# RedCarMotorControllerBoard.net
KiCad netlist of a schematic drawn in EAGLE
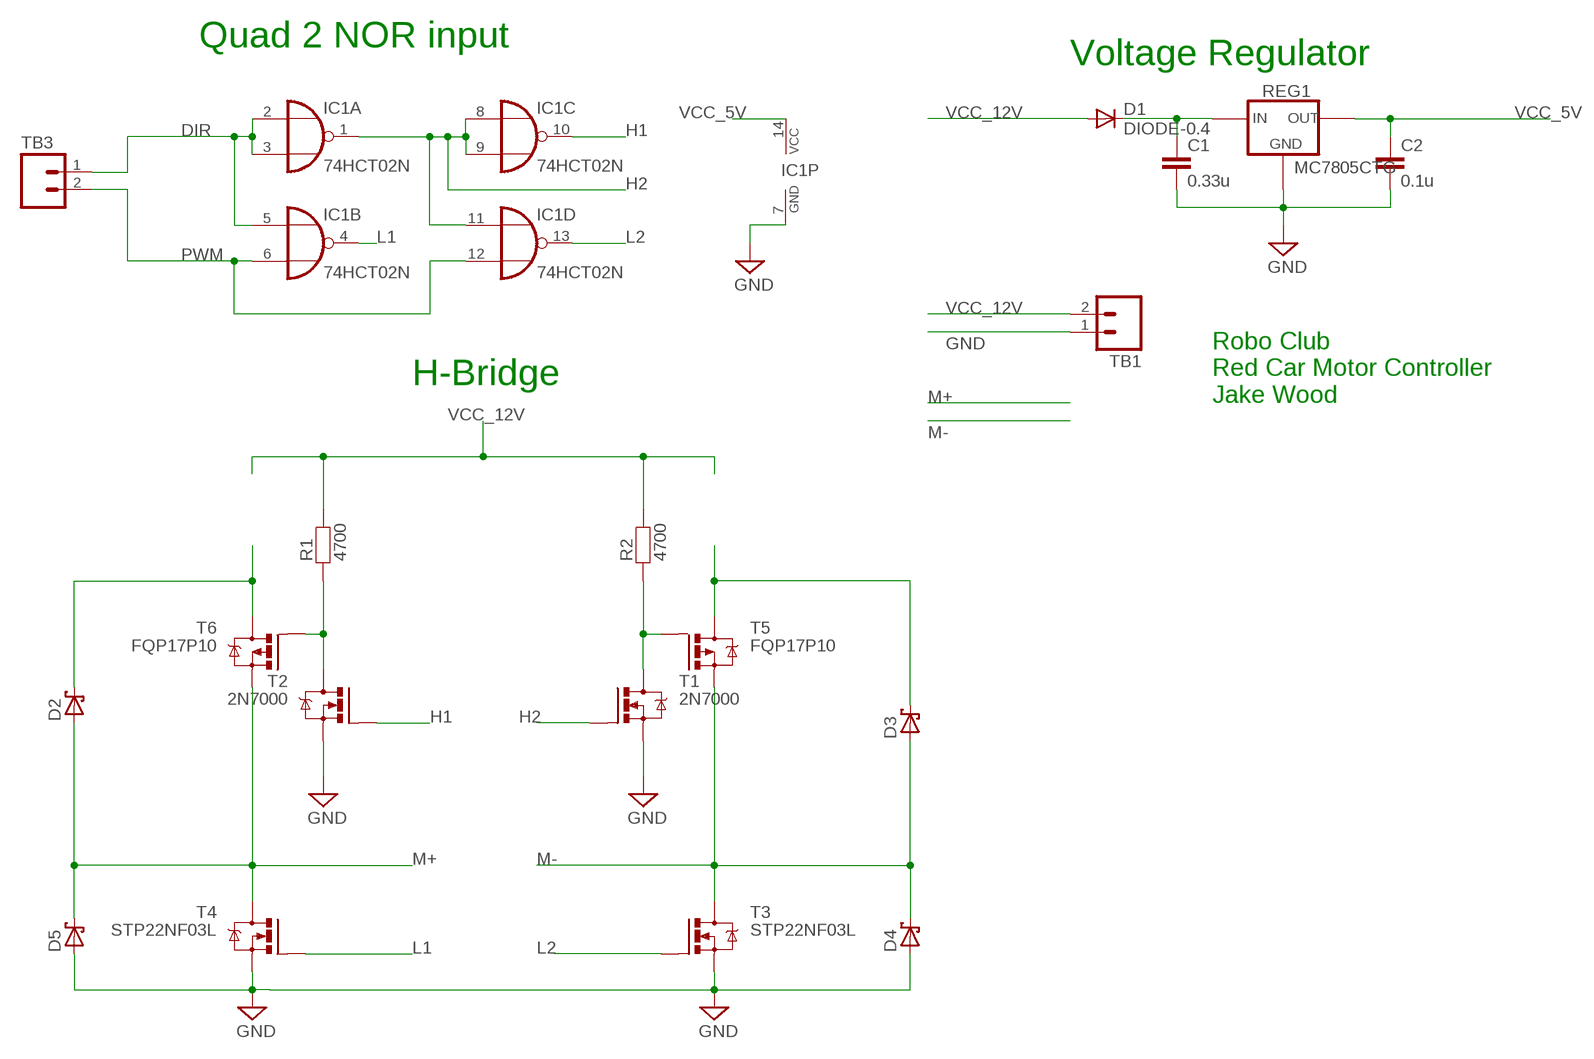
[diagram p0: schematic, sheet 1]

(export (version "E")
  (design (tool "Eeschema 10.0.6"))
  (components
    (comp (ref "C1")
      (value "0.33u")
      (footprint "eagle-import:RADIAL-0.2")
      (libsource (lib "eagle-import") (part "CAPACITOR-RADIAL-0.2"))
    )
    (comp (ref "C2")
      (value "0.1u")
      (footprint "eagle-import:RADIAL-0.2")
      (libsource (lib "eagle-import") (part "CAPACITOR-RADIAL-0.2"))
    )
    (comp (ref "D1")
      (value "DIODE-0.4")
      (footprint "eagle-import:DIODE-0.4")
      (libsource (lib "eagle-import") (part "DIODE-0.4"))
    )
    (comp (ref "D2")
      (value "SCHOTTKY-DIODEDO201T15")
      (footprint "eagle-import:DO201T15")
      (libsource (lib "eagle-import") (part "SCHOTTKY-DIODEDO201T15"))
    )
    (comp (ref "D3")
      (value "SCHOTTKY-DIODEDO201T15")
      (footprint "eagle-import:DO201T15")
      (libsource (lib "eagle-import") (part "SCHOTTKY-DIODEDO201T15"))
    )
    (comp (ref "D4")
      (value "SCHOTTKY-DIODEDO201T15")
      (footprint "eagle-import:DO201T15")
      (libsource (lib "eagle-import") (part "SCHOTTKY-DIODEDO201T15"))
    )
    (comp (ref "D5")
      (value "SCHOTTKY-DIODEDO201T15")
      (footprint "eagle-import:DO201T15")
      (libsource (lib "eagle-import") (part "SCHOTTKY-DIODEDO201T15"))
    )
    (comp (ref "IC1")
      (value "74HCT02N")
      (footprint "eagle-import:DIL14")
      (libsource (lib "eagle-import") (part "7402NHCT"))
    )
    (comp (ref "R1")
      (value "4700")
      (footprint "eagle-import:AXIAL-0.4")
      (libsource (lib "eagle-import") (part "RESISTOR-AXIAL-0.4"))
    )
    (comp (ref "R2")
      (value "4700")
      (footprint "eagle-import:AXIAL-0.4")
      (libsource (lib "eagle-import") (part "RESISTOR-AXIAL-0.4"))
    )
    (comp (ref "REG1")
      (value "MC7805CTG")
      (footprint "eagle-import:TO220-UPRIGHT")
      (libsource (lib "eagle-import") (part "MC7805CTG"))
    )
    (comp (ref "T1")
      (value "2N7000")
      (footprint "eagle-import:TO92-")
      (libsource (lib "eagle-import") (part "2N7000"))
    )
    (comp (ref "T2")
      (value "2N7000")
      (footprint "eagle-import:TO92-")
      (libsource (lib "eagle-import") (part "2N7000"))
    )
    (comp (ref "T3")
      (value "STP22NF03L")
      (footprint "eagle-import:TO220-UPRIGHT")
      (libsource (lib "eagle-import") (part "STP22NF03L"))
    )
    (comp (ref "T4")
      (value "STP22NF03L")
      (footprint "eagle-import:TO220-UPRIGHT")
      (libsource (lib "eagle-import") (part "STP22NF03L"))
    )
    (comp (ref "T5")
      (value "FQP17P10")
      (footprint "eagle-import:TO220-UPRIGHT")
      (libsource (lib "eagle-import") (part "FQP17P10"))
    )
    (comp (ref "T6")
      (value "FQP17P10")
      (footprint "eagle-import:TO220-UPRIGHT")
      (libsource (lib "eagle-import") (part "FQP17P10"))
    )
    (comp (ref "TB1")
      (value "KK-CONNECT-2WAY_PG")
      (footprint "eagle-import:KK-CONNECT-2WAY-PG")
      (libsource (lib "eagle-import") (part "KK-CONNECT-2WAY_PG"))
    )
    (comp (ref "TB3")
      (value "KK-CONNECT-2WAY_PG")
      (footprint "eagle-import:KK-CONNECT-2WAY-PG")
      (libsource (lib "eagle-import") (part "KK-CONNECT-2WAY_PG"))
    )
  )
  (nets
    (net (code "1") (name "/DIR") (class "Default")
      (node (ref "IC1") (pin "2") (pinfunction "I0_2") (pintype "input"))
      (node (ref "IC1") (pin "3") (pinfunction "I1_3") (pintype "input"))
      (node (ref "IC1") (pin "5") (pinfunction "I0_5") (pintype "input"))
      (node (ref "TB3") (pin "1") (pinfunction "1_1") (pintype "passive"))
    )
    (net (code "2") (name "/H1") (class "Default")
      (node (ref "IC1") (pin "10") (pinfunction "O_10") (pintype "output"))
      (node (ref "T2") (pin "2") (pinfunction "G_2") (pintype "passive"))
    )
    (net (code "3") (name "/H2") (class "Default")
      (node (ref "IC1") (pin "1") (pinfunction "O_1") (pintype "output"))
      (node (ref "IC1") (pin "11") (pinfunction "I0_11") (pintype "input"))
      (node (ref "IC1") (pin "8") (pinfunction "I0_8") (pintype "input"))
      (node (ref "IC1") (pin "9") (pinfunction "I1_9") (pintype "input"))
      (node (ref "T1") (pin "2") (pinfunction "G_2") (pintype "passive"))
    )
    (net (code "4") (name "/L1") (class "Default")
      (node (ref "IC1") (pin "4") (pinfunction "O_4") (pintype "output"))
      (node (ref "T4") (pin "1") (pinfunction "G_1") (pintype "passive"))
    )
    (net (code "5") (name "/L2") (class "Default")
      (node (ref "IC1") (pin "13") (pinfunction "O_13") (pintype "output"))
      (node (ref "T3") (pin "1") (pinfunction "G_1") (pintype "passive"))
    )
    (net (code "6") (name "/M+") (class "Default")
      (node (ref "D2") (pin "A") (pinfunction "A_A") (pintype "passive"))
      (node (ref "D5") (pin "C") (pinfunction "C_C") (pintype "passive"))
      (node (ref "T4") (pin "2") (pinfunction "D_2") (pintype "passive"))
      (node (ref "T6") (pin "2") (pinfunction "D_2") (pintype "passive"))
    )
    (net (code "7") (name "/M-") (class "Default")
      (node (ref "D3") (pin "A") (pinfunction "A_A") (pintype "passive"))
      (node (ref "D4") (pin "C") (pinfunction "C_C") (pintype "passive"))
      (node (ref "T3") (pin "2") (pinfunction "D_2") (pintype "passive"))
      (node (ref "T5") (pin "2") (pinfunction "D_2") (pintype "passive"))
    )
    (net (code "8") (name "/PWM") (class "Default")
      (node (ref "IC1") (pin "12") (pinfunction "I1_12") (pintype "input"))
      (node (ref "IC1") (pin "6") (pinfunction "I1_6") (pintype "input"))
      (node (ref "TB3") (pin "2") (pinfunction "2_2") (pintype "passive"))
    )
    (net (code "9") (name "/VCC_5V") (class "Default")
      (node (ref "C2") (pin "P$1") (pinfunction "1_P$1") (pintype "passive"))
      (node (ref "IC1") (pin "14") (pinfunction "VCC_14") (pintype "power_in"))
      (node (ref "REG1") (pin "3") (pinfunction "OUT_3") (pintype "output"))
    )
    (net (code "10") (name "/VCC_12V") (class "Default")
      (node (ref "D1") (pin "A") (pinfunction "A_A") (pintype "passive"))
      (node (ref "R1") (pin "P$2") (pinfunction "2_P$2") (pintype "passive"))
      (node (ref "R2") (pin "P$2") (pinfunction "2_P$2") (pintype "passive"))
      (node (ref "TB1") (pin "2") (pinfunction "2_2") (pintype "passive"))
    )
    (net (code "11") (name "GND") (class "Default")
      (node (ref "C1") (pin "P$2") (pinfunction "2_P$2") (pintype "passive"))
      (node (ref "C2") (pin "P$2") (pinfunction "2_P$2") (pintype "passive"))
      (node (ref "D4") (pin "A") (pinfunction "A_A") (pintype "passive"))
      (node (ref "D5") (pin "A") (pinfunction "A_A") (pintype "passive"))
      (node (ref "IC1") (pin "7") (pinfunction "GND_7") (pintype "power_in"))
      (node (ref "REG1") (pin "2") (pinfunction "GND_2") (pintype "power_in"))
      (node (ref "T1") (pin "3") (pinfunction "S_3") (pintype "passive"))
      (node (ref "T2") (pin "3") (pinfunction "S_3") (pintype "passive"))
      (node (ref "T3") (pin "3") (pinfunction "S_3") (pintype "passive"))
      (node (ref "T4") (pin "3") (pinfunction "S_3") (pintype "passive"))
      (node (ref "TB1") (pin "1") (pinfunction "1_1") (pintype "passive"))
    )
    (net (code "12") (name "Net-(C1-1)") (class "Default")
      (node (ref "C1") (pin "P$1") (pinfunction "1_P$1") (pintype "passive"))
      (node (ref "D1") (pin "C") (pinfunction "C_C") (pintype "passive"))
      (node (ref "REG1") (pin "1") (pinfunction "IN_1") (pintype "input"))
    )
    (net (code "13") (name "Net-(R1-1)") (class "Default")
      (node (ref "R1") (pin "P$1") (pinfunction "1_P$1") (pintype "passive"))
      (node (ref "T2") (pin "1") (pinfunction "D_1") (pintype "passive"))
      (node (ref "T6") (pin "1") (pinfunction "G_1") (pintype "passive"))
    )
    (net (code "14") (name "Net-(R2-1)") (class "Default")
      (node (ref "R2") (pin "P$1") (pinfunction "1_P$1") (pintype "passive"))
      (node (ref "T1") (pin "1") (pinfunction "D_1") (pintype "passive"))
      (node (ref "T5") (pin "1") (pinfunction "G_1") (pintype "passive"))
    )
    (net (code "15") (name "Net-(T5-S)") (class "Default")
      (node (ref "D3") (pin "C") (pinfunction "C_C") (pintype "passive"))
      (node (ref "T5") (pin "3") (pinfunction "S_3") (pintype "passive"))
    )
    (net (code "16") (name "Net-(T6-S)") (class "Default")
      (node (ref "D2") (pin "C") (pinfunction "C_C") (pintype "passive"))
      (node (ref "T6") (pin "3") (pinfunction "S_3") (pintype "passive"))
    )
  )
)
